# LED-single-sided-front.net
KiCad netlist of a schematic drawn in EAGLE
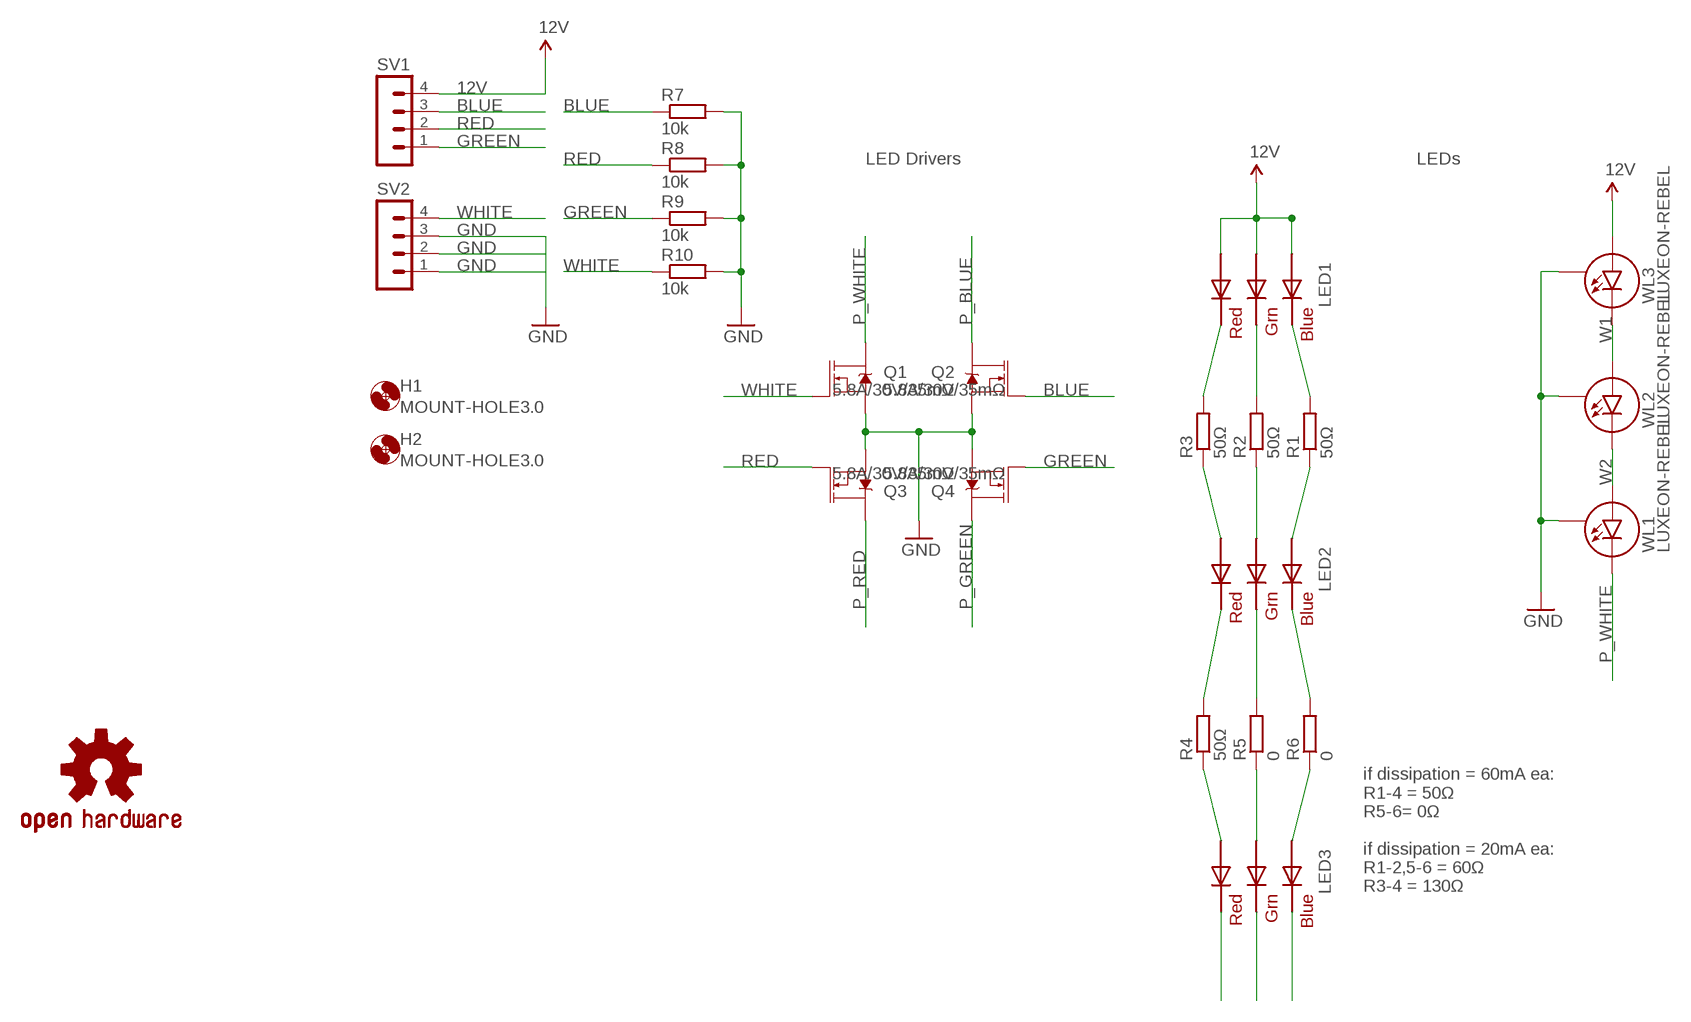
[diagram p0: schematic, sheet 1]

(export (version "E")
  (design (tool "Eeschema 10.0.6"))
  (components
    (comp (ref "H1")
      (value "MOUNT-HOLE3.0")
      (footprint "eagle-import:3,0")
      (libsource (lib "eagle-import") (part "MOUNT-HOLE3.0"))
    )
    (comp (ref "H2")
      (value "MOUNT-HOLE3.0")
      (footprint "eagle-import:3,0")
      (libsource (lib "eagle-import") (part "MOUNT-HOLE3.0"))
    )
    (comp (ref "LED1")
      (value "RGBLED5050")
      (footprint "eagle-import:RGBLED5050")
      (libsource (lib "eagle-import") (part "RGBLED5050"))
    )
    (comp (ref "LED2")
      (value "RGBLED5050")
      (footprint "eagle-import:RGBLED5050")
      (libsource (lib "eagle-import") (part "RGBLED5050"))
    )
    (comp (ref "LED3")
      (value "RGBLED5050")
      (footprint "eagle-import:RGBLED5050")
      (libsource (lib "eagle-import") (part "RGBLED5050"))
    )
    (comp (ref "LOGO1")
      (value "OSHW-LOGOS")
      (footprint "eagle-import:OSHW-LOGO-S")
      (libsource (lib "eagle-import") (part "OSHW-LOGOS"))
    )
    (comp (ref "Q1")
      (value "5.8A/30V/35mΩ")
      (footprint "eagle-import:SOT23-3")
      (libsource (lib "eagle-import") (part "MOSFET-NCH-AO3404A"))
    )
    (comp (ref "Q2")
      (value "5.8A/30V/35mΩ")
      (footprint "eagle-import:SOT23-3")
      (libsource (lib "eagle-import") (part "MOSFET-NCH-AO3404A"))
    )
    (comp (ref "Q3")
      (value "5.8A/30V/35mΩ")
      (footprint "eagle-import:SOT23-3")
      (libsource (lib "eagle-import") (part "MOSFET-NCH-AO3404A"))
    )
    (comp (ref "Q4")
      (value "5.8A/30V/35mΩ")
      (footprint "eagle-import:SOT23-3")
      (libsource (lib "eagle-import") (part "MOSFET-NCH-AO3404A"))
    )
    (comp (ref "R1")
      (value "50Ω")
      (footprint "eagle-import:R1206")
      (libsource (lib "eagle-import") (part "R-EU_R1206"))
    )
    (comp (ref "R2")
      (value "50Ω")
      (footprint "eagle-import:R1206")
      (libsource (lib "eagle-import") (part "R-EU_R1206"))
    )
    (comp (ref "R3")
      (value "50Ω")
      (footprint "eagle-import:R1206")
      (libsource (lib "eagle-import") (part "R-EU_R1206"))
    )
    (comp (ref "R4")
      (value "50Ω")
      (footprint "eagle-import:R1206")
      (libsource (lib "eagle-import") (part "R-EU_R1206"))
    )
    (comp (ref "R5")
      (value "0")
      (footprint "eagle-import:R1206")
      (libsource (lib "eagle-import") (part "R-EU_R1206"))
    )
    (comp (ref "R6")
      (value "0")
      (footprint "eagle-import:R1206")
      (libsource (lib "eagle-import") (part "R-EU_R1206"))
    )
    (comp (ref "R7")
      (value "10k")
      (footprint "eagle-import:R1206")
      (libsource (lib "eagle-import") (part "R-EU_R1206"))
    )
    (comp (ref "R8")
      (value "10k")
      (footprint "eagle-import:R1206")
      (libsource (lib "eagle-import") (part "R-EU_R1206"))
    )
    (comp (ref "R9")
      (value "10k")
      (footprint "eagle-import:R1206")
      (libsource (lib "eagle-import") (part "R-EU_R1206"))
    )
    (comp (ref "R10")
      (value "10k")
      (footprint "eagle-import:R1206")
      (libsource (lib "eagle-import") (part "R-EU_R1206"))
    )
    (comp (ref "SV1")
      (value "MA04-1")
      (footprint "eagle-import:MA04-1")
      (libsource (lib "eagle-import") (part "MA04-1"))
    )
    (comp (ref "SV2")
      (value "MA04-1")
      (footprint "eagle-import:MA04-1")
      (libsource (lib "eagle-import") (part "MA04-1"))
    )
    (comp (ref "WL1")
      (value "LUXEON-REBEL")
      (footprint "eagle-import:LUXEON-REBEL")
      (libsource (lib "eagle-import") (part "LUXEON-REBEL"))
    )
    (comp (ref "WL2")
      (value "LUXEON-REBEL")
      (footprint "eagle-import:LUXEON-REBEL")
      (libsource (lib "eagle-import") (part "LUXEON-REBEL"))
    )
    (comp (ref "WL3")
      (value "LUXEON-REBEL")
      (footprint "eagle-import:LUXEON-REBEL")
      (libsource (lib "eagle-import") (part "LUXEON-REBEL"))
    )
  )
  (nets
    (net (code "1") (name "/BLUE") (class "Default")
      (node (ref "Q2") (pin "1") (pinfunction "G_1") (pintype "bidirectional"))
      (node (ref "R7") (pin "1") (pinfunction "1_1") (pintype "passive"))
      (node (ref "SV1") (pin "3") (pinfunction "3_3") (pintype "passive"))
    )
    (net (code "2") (name "/GREEN") (class "Default")
      (node (ref "Q4") (pin "1") (pinfunction "G_1") (pintype "bidirectional"))
      (node (ref "R9") (pin "1") (pinfunction "1_1") (pintype "passive"))
      (node (ref "SV1") (pin "1") (pinfunction "1_1") (pintype "passive"))
    )
    (net (code "3") (name "/P_BLUE") (class "Default")
      (node (ref "LED3") (pin "4") (pinfunction "BLUE_C_4") (pintype "bidirectional"))
      (node (ref "Q2") (pin "3") (pinfunction "D_3") (pintype "bidirectional"))
    )
    (net (code "4") (name "/P_GREEN") (class "Default")
      (node (ref "LED3") (pin "6") (pinfunction "GREEN_C_6") (pintype "bidirectional"))
      (node (ref "Q4") (pin "3") (pinfunction "D_3") (pintype "bidirectional"))
    )
    (net (code "5") (name "/P_RED") (class "Default")
      (node (ref "LED3") (pin "5") (pinfunction "RED_C_5") (pintype "bidirectional"))
      (node (ref "Q3") (pin "3") (pinfunction "D_3") (pintype "bidirectional"))
    )
    (net (code "6") (name "/P_WHITE") (class "Default")
      (node (ref "Q1") (pin "3") (pinfunction "D_3") (pintype "bidirectional"))
      (node (ref "WL1") (pin "CATHODE") (pinfunction "C_CATHODE") (pintype "passive"))
    )
    (net (code "7") (name "/RED") (class "Default")
      (node (ref "Q3") (pin "1") (pinfunction "G_1") (pintype "bidirectional"))
      (node (ref "R8") (pin "1") (pinfunction "1_1") (pintype "passive"))
      (node (ref "SV1") (pin "2") (pinfunction "2_2") (pintype "passive"))
    )
    (net (code "8") (name "/W1") (class "Default")
      (node (ref "WL2") (pin "ANODE") (pinfunction "A_ANODE") (pintype "passive"))
      (node (ref "WL3") (pin "CATHODE") (pinfunction "C_CATHODE") (pintype "passive"))
    )
    (net (code "9") (name "/W2") (class "Default")
      (node (ref "WL1") (pin "ANODE") (pinfunction "A_ANODE") (pintype "passive"))
      (node (ref "WL2") (pin "CATHODE") (pinfunction "C_CATHODE") (pintype "passive"))
    )
    (net (code "10") (name "/WHITE") (class "Default")
      (node (ref "Q1") (pin "1") (pinfunction "G_1") (pintype "bidirectional"))
      (node (ref "R10") (pin "1") (pinfunction "1_1") (pintype "passive"))
      (node (ref "SV2") (pin "4") (pinfunction "4_4") (pintype "passive"))
    )
    (net (code "11") (name "12V") (class "Default")
      (node (ref "LED1") (pin "1") (pinfunction "GREEN_A_1") (pintype "bidirectional"))
      (node (ref "LED1") (pin "2") (pinfunction "RED_A_2") (pintype "bidirectional"))
      (node (ref "LED1") (pin "3") (pinfunction "BLUE_A_3") (pintype "bidirectional"))
      (node (ref "SV1") (pin "4") (pinfunction "4_4") (pintype "passive"))
      (node (ref "WL3") (pin "ANODE") (pinfunction "A_ANODE") (pintype "passive"))
    )
    (net (code "12") (name "GND") (class "Default")
      (node (ref "Q1") (pin "2") (pinfunction "S_2") (pintype "bidirectional"))
      (node (ref "Q2") (pin "2") (pinfunction "S_2") (pintype "bidirectional"))
      (node (ref "Q3") (pin "2") (pinfunction "S_2") (pintype "bidirectional"))
      (node (ref "Q4") (pin "2") (pinfunction "S_2") (pintype "bidirectional"))
      (node (ref "R10") (pin "2") (pinfunction "2_2") (pintype "passive"))
      (node (ref "R7") (pin "2") (pinfunction "2_2") (pintype "passive"))
      (node (ref "R8") (pin "2") (pinfunction "2_2") (pintype "passive"))
      (node (ref "R9") (pin "2") (pinfunction "2_2") (pintype "passive"))
      (node (ref "SV2") (pin "1") (pinfunction "1_1") (pintype "passive"))
      (node (ref "SV2") (pin "2") (pinfunction "2_2") (pintype "passive"))
      (node (ref "SV2") (pin "3") (pinfunction "3_3") (pintype "passive"))
      (node (ref "WL1") (pin "P$3") (pinfunction "S_P$3") (pintype "bidirectional"))
      (node (ref "WL2") (pin "P$3") (pinfunction "S_P$3") (pintype "bidirectional"))
      (node (ref "WL3") (pin "P$3") (pinfunction "S_P$3") (pintype "bidirectional"))
    )
    (net (code "13") (name "Net-(LED1-BLUE_C)") (class "Default")
      (node (ref "LED1") (pin "4") (pinfunction "BLUE_C_4") (pintype "bidirectional"))
      (node (ref "R1") (pin "2") (pinfunction "2_2") (pintype "passive"))
    )
    (net (code "14") (name "Net-(LED1-GREEN_C)") (class "Default")
      (node (ref "LED1") (pin "6") (pinfunction "GREEN_C_6") (pintype "bidirectional"))
      (node (ref "R2") (pin "2") (pinfunction "2_2") (pintype "passive"))
    )
    (net (code "15") (name "Net-(LED1-RED_C)") (class "Default")
      (node (ref "LED1") (pin "5") (pinfunction "RED_C_5") (pintype "bidirectional"))
      (node (ref "R3") (pin "2") (pinfunction "2_2") (pintype "passive"))
    )
    (net (code "16") (name "Net-(LED2-BLUE_A)") (class "Default")
      (node (ref "LED2") (pin "3") (pinfunction "BLUE_A_3") (pintype "bidirectional"))
      (node (ref "R1") (pin "1") (pinfunction "1_1") (pintype "passive"))
    )
    (net (code "17") (name "Net-(LED2-BLUE_C)") (class "Default")
      (node (ref "LED2") (pin "4") (pinfunction "BLUE_C_4") (pintype "bidirectional"))
      (node (ref "R6") (pin "2") (pinfunction "2_2") (pintype "passive"))
    )
    (net (code "18") (name "Net-(LED2-GREEN_A)") (class "Default")
      (node (ref "LED2") (pin "1") (pinfunction "GREEN_A_1") (pintype "bidirectional"))
      (node (ref "R2") (pin "1") (pinfunction "1_1") (pintype "passive"))
    )
    (net (code "19") (name "Net-(LED2-GREEN_C)") (class "Default")
      (node (ref "LED2") (pin "6") (pinfunction "GREEN_C_6") (pintype "bidirectional"))
      (node (ref "R5") (pin "2") (pinfunction "2_2") (pintype "passive"))
    )
    (net (code "20") (name "Net-(LED2-RED_A)") (class "Default")
      (node (ref "LED2") (pin "2") (pinfunction "RED_A_2") (pintype "bidirectional"))
      (node (ref "R3") (pin "1") (pinfunction "1_1") (pintype "passive"))
    )
    (net (code "21") (name "Net-(LED2-RED_C)") (class "Default")
      (node (ref "LED2") (pin "5") (pinfunction "RED_C_5") (pintype "bidirectional"))
      (node (ref "R4") (pin "2") (pinfunction "2_2") (pintype "passive"))
    )
    (net (code "22") (name "Net-(LED3-BLUE_A)") (class "Default")
      (node (ref "LED3") (pin "3") (pinfunction "BLUE_A_3") (pintype "bidirectional"))
      (node (ref "R6") (pin "1") (pinfunction "1_1") (pintype "passive"))
    )
    (net (code "23") (name "Net-(LED3-GREEN_A)") (class "Default")
      (node (ref "LED3") (pin "1") (pinfunction "GREEN_A_1") (pintype "bidirectional"))
      (node (ref "R5") (pin "1") (pinfunction "1_1") (pintype "passive"))
    )
    (net (code "24") (name "Net-(LED3-RED_A)") (class "Default")
      (node (ref "LED3") (pin "2") (pinfunction "RED_A_2") (pintype "bidirectional"))
      (node (ref "R4") (pin "1") (pinfunction "1_1") (pintype "passive"))
    )
  )
)
